# LVDS.net
KiCad netlist of a schematic drawn in Altium Designer
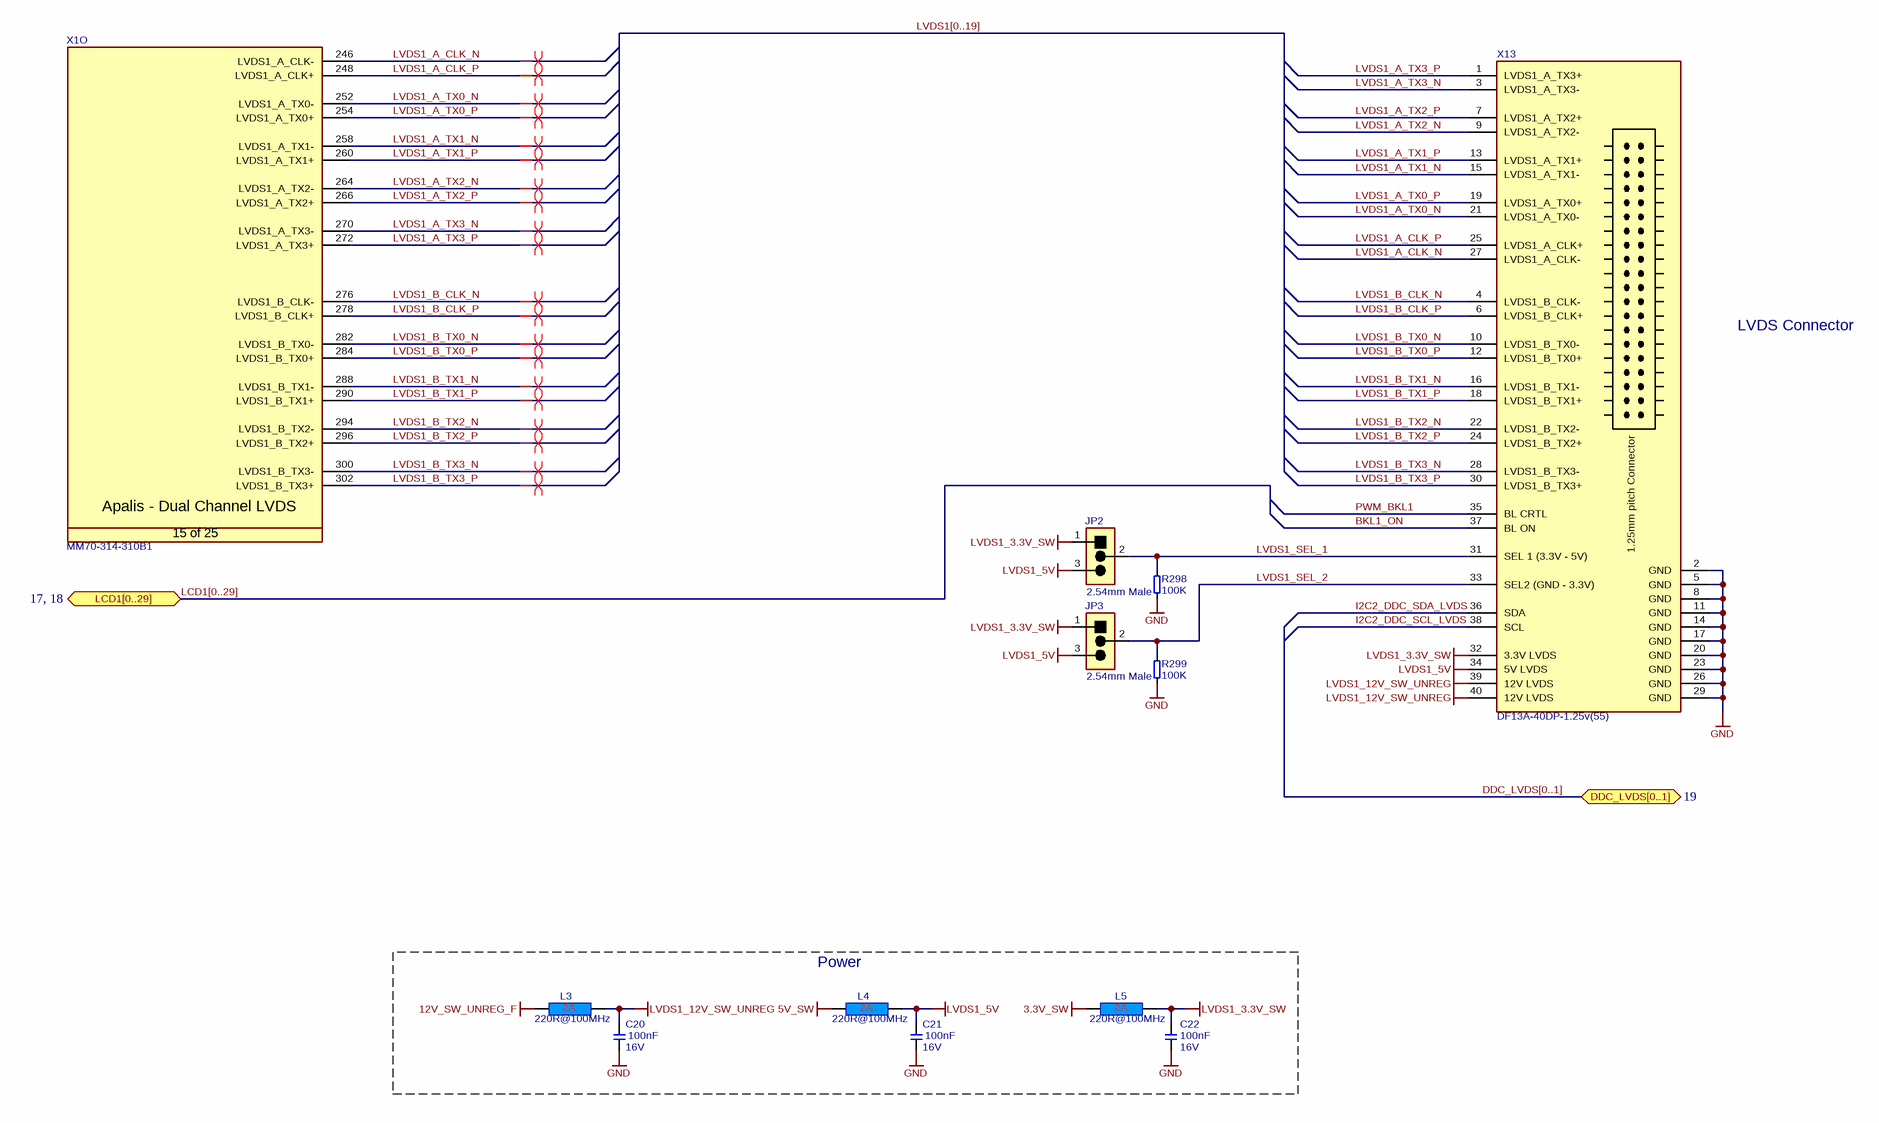
[diagram p0: LVDS.SchDoc]

(export (version "E")
  (design (tool "Eeschema 10.0.6"))
  (components
    (comp (ref "C20")
      (value "100nF")
      (footprint "T_CAPC0603X33N")
      (description "Capacitor Ceramic X7R 100nF 16V 10% 0603")
      (fields (field (name "TOLERANCE") "10%") (field (name "RATING") "16V"))
      (libsource (lib "Apalis Evaluation Board") (part "C-X7R-100nF-16V-10%-0603"))
    )
    (comp (ref "C21")
      (value "100nF")
      (footprint "T_CAPC0603X33N")
      (description "Capacitor Ceramic X7R 100nF 16V 10% 0603")
      (fields (field (name "TOLERANCE") "10%") (field (name "RATING") "16V"))
      (libsource (lib "Apalis Evaluation Board") (part "C-X7R-100nF-16V-10%-0603"))
    )
    (comp (ref "C22")
      (value "100nF")
      (footprint "T_CAPC0603X33N")
      (description "Capacitor Ceramic X7R 100nF 16V 10% 0603")
      (fields (field (name "TOLERANCE") "10%") (field (name "RATING") "16V"))
      (libsource (lib "Apalis Evaluation Board") (part "C-X7R-100nF-16V-10%-0603"))
    )
    (comp (ref "JP2")
      (value "826936-3")
      (footprint "T_TYCO_826936-3")
      (description "Jumper, 3-Pin")
      (libsource (lib "Apalis Evaluation Board") (part "CON-Tyco-826936-3-1X3-2.54mm-JP"))
    )
    (comp (ref "JP3")
      (value "826936-3")
      (footprint "T_TYCO_826936-3")
      (description "Jumper, 3-Pin")
      (libsource (lib "Apalis Evaluation Board") (part "CON-Tyco-826936-3-1X3-2.54mm-JP"))
    )
    (comp (ref "L3")
      (value "220R@100MHz")
      (footprint "INDC1608X95N")
      (description "220R@100MHz 2A EMI FILTER")
      (fields (field (name "TOLERANCE") "25%"))
      (libsource (lib "Apalis Evaluation Board") (part "L-220R@100MHz-2A-25%-0603"))
    )
    (comp (ref "L4")
      (value "220R@100MHz")
      (footprint "INDC1608X95N")
      (description "220R@100MHz 2A EMI FILTER")
      (fields (field (name "TOLERANCE") "25%"))
      (libsource (lib "Apalis Evaluation Board") (part "L-220R@100MHz-2A-25%-0603"))
    )
    (comp (ref "L5")
      (value "220R@100MHz")
      (footprint "INDC1608X95N")
      (description "220R@100MHz 2A EMI FILTER")
      (fields (field (name "TOLERANCE") "25%"))
      (libsource (lib "Apalis Evaluation Board") (part "L-220R@100MHz-2A-25%-0603"))
    )
    (comp (ref "R298")
      (value "100K")
      (footprint "T_RESC0603X30N")
      (description "Resistor 100 Kohm 63mW 5% 0603")
      (fields (field (name "TOLERANCE") "5%"))
      (libsource (lib "Apalis Evaluation Board") (part "R-100KR-63mW-5%-0603"))
    )
    (comp (ref "R299")
      (value "100K")
      (footprint "T_RESC0603X30N")
      (description "Resistor 100 Kohm 63mW 5% 0603")
      (fields (field (name "TOLERANCE") "5%"))
      (libsource (lib "Apalis Evaluation Board") (part "R-100KR-63mW-5%-0603"))
    )
    (comp (ref "X1")
      (value "CON-JAE-MM70-314-310B1-314-0.5mm")
      (footprint "T_JAE_MM70-314-310B1")
      (description "MXM3 Connector")
      (fields (field (name "MANUFACTURER PART NO.") "MM70-314-310B1"))
      (libsource (lib "Apalis Evaluation Board") (part "CON-JAE-MM70-314-310B1-314-0.5mm"))
    )
    (comp (ref "X13")
      (value "CON-Hirose-DF13A-40DP-1.25v(55)-2x10-1mm")
      (footprint "T_HIROSE_DF13A-40DP-1.25V(55)")
      (description "LVDS Connector")
      (fields (field (name "MANUFACTURER PART NO.") "DF13A-40DP-1.25v(55)"))
      (libsource (lib "Apalis Evaluation Board") (part "CON-Hirose-DF13A-40DP-1.25v(55)-2x20-1.25mm"))
    )
  )
  (nets
    (net (code "53") (name "/BKL1_ON") (class "Default")
      (node (ref "X13") (pin "37") (pinfunction "BL_ON_37") (pintype "passive"))
    )
    (net (code "55") (name "/I2C2_DDC_SCL_LVDS") (class "Default")
      (node (ref "X13") (pin "38") (pinfunction "SCL_38") (pintype "passive"))
    )
    (net (code "56") (name "/I2C2_DDC_SDA_LVDS") (class "Default")
      (node (ref "X13") (pin "36") (pinfunction "SDA_36") (pintype "passive"))
    )
    (net (code "59") (name "/LVDS1_A_CLK_N") (class "Default")
      (node (ref "X1") (pin "246") (pinfunction "LVDS1_A_CLK-_246") (pintype "passive"))
      (node (ref "X13") (pin "27") (pinfunction "LVDS1_A_CLK-_27") (pintype "passive"))
    )
    (net (code "60") (name "/LVDS1_A_CLK_P") (class "Default")
      (node (ref "X1") (pin "248") (pinfunction "LVDS1_A_CLK+_248") (pintype "passive"))
      (node (ref "X13") (pin "25") (pinfunction "LVDS1_A_CLK+_25") (pintype "passive"))
    )
    (net (code "61") (name "/LVDS1_A_TX0_N") (class "Default")
      (node (ref "X1") (pin "252") (pinfunction "LVDS1_A_TX0-_252") (pintype "passive"))
      (node (ref "X13") (pin "21") (pinfunction "LVDS1_A_TX0-_21") (pintype "passive"))
    )
    (net (code "62") (name "/LVDS1_A_TX0_P") (class "Default")
      (node (ref "X1") (pin "254") (pinfunction "LVDS1_A_TX0+_254") (pintype "passive"))
      (node (ref "X13") (pin "19") (pinfunction "LVDS1_A_TX0+_19") (pintype "passive"))
    )
    (net (code "63") (name "/LVDS1_A_TX1_N") (class "Default")
      (node (ref "X1") (pin "258") (pinfunction "LVDS1_A_TX1-_258") (pintype "passive"))
      (node (ref "X13") (pin "15") (pinfunction "LVDS1_A_TX1-_15") (pintype "passive"))
    )
    (net (code "64") (name "/LVDS1_A_TX1_P") (class "Default")
      (node (ref "X1") (pin "260") (pinfunction "LVDS1_A_TX1+_260") (pintype "passive"))
      (node (ref "X13") (pin "13") (pinfunction "LVDS1_A_TX1+_13") (pintype "passive"))
    )
    (net (code "65") (name "/LVDS1_A_TX2_N") (class "Default")
      (node (ref "X1") (pin "264") (pinfunction "LVDS1_A_TX2-_264") (pintype "passive"))
      (node (ref "X13") (pin "9") (pinfunction "LVDS1_A_TX2-_9") (pintype "passive"))
    )
    (net (code "66") (name "/LVDS1_A_TX2_P") (class "Default")
      (node (ref "X1") (pin "266") (pinfunction "LVDS1_A_TX2+_266") (pintype "passive"))
      (node (ref "X13") (pin "7") (pinfunction "LVDS1_A_TX2+_7") (pintype "passive"))
    )
    (net (code "67") (name "/LVDS1_A_TX3_N") (class "Default")
      (node (ref "X1") (pin "270") (pinfunction "LVDS1_A_TX3-_270") (pintype "passive"))
      (node (ref "X13") (pin "3") (pinfunction "LVDS1_A_TX3-_3") (pintype "passive"))
    )
    (net (code "68") (name "/LVDS1_A_TX3_P") (class "Default")
      (node (ref "X1") (pin "272") (pinfunction "LVDS1_A_TX3+_272") (pintype "passive"))
      (node (ref "X13") (pin "1") (pinfunction "LVDS1_A_TX3+_1") (pintype "passive"))
    )
    (net (code "69") (name "/LVDS1_B_CLK_N") (class "Default")
      (node (ref "X1") (pin "276") (pinfunction "LVDS1_B_CLK-_276") (pintype "passive"))
      (node (ref "X13") (pin "4") (pinfunction "LVDS1_B_CLK-_4") (pintype "passive"))
    )
    (net (code "70") (name "/LVDS1_B_CLK_P") (class "Default")
      (node (ref "X1") (pin "278") (pinfunction "LVDS1_B_CLK+_278") (pintype "passive"))
      (node (ref "X13") (pin "6") (pinfunction "LVDS1_B_CLK+_6") (pintype "passive"))
    )
    (net (code "71") (name "/LVDS1_B_TX0_N") (class "Default")
      (node (ref "X1") (pin "282") (pinfunction "LVDS1_B_TX0-_282") (pintype "passive"))
      (node (ref "X13") (pin "10") (pinfunction "LVDS1_B_TX0-_10") (pintype "passive"))
    )
    (net (code "72") (name "/LVDS1_B_TX0_P") (class "Default")
      (node (ref "X1") (pin "284") (pinfunction "LVDS1_B_TX0+_284") (pintype "passive"))
      (node (ref "X13") (pin "12") (pinfunction "LVDS1_B_TX0+_12") (pintype "passive"))
    )
    (net (code "73") (name "/LVDS1_B_TX1_N") (class "Default")
      (node (ref "X1") (pin "288") (pinfunction "LVDS1_B_TX1-_288") (pintype "passive"))
      (node (ref "X13") (pin "16") (pinfunction "LVDS1_B_TX1-_16") (pintype "passive"))
    )
    (net (code "74") (name "/LVDS1_B_TX1_P") (class "Default")
      (node (ref "X1") (pin "290") (pinfunction "LVDS1_B_TX1+_290") (pintype "passive"))
      (node (ref "X13") (pin "18") (pinfunction "LVDS1_B_TX1+_18") (pintype "passive"))
    )
    (net (code "75") (name "/LVDS1_B_TX2_N") (class "Default")
      (node (ref "X1") (pin "294") (pinfunction "LVDS1_B_TX2-_294") (pintype "passive"))
      (node (ref "X13") (pin "22") (pinfunction "LVDS1_B_TX2-_22") (pintype "passive"))
    )
    (net (code "76") (name "/LVDS1_B_TX2_P") (class "Default")
      (node (ref "X1") (pin "296") (pinfunction "LVDS1_B_TX2+_296") (pintype "passive"))
      (node (ref "X13") (pin "24") (pinfunction "LVDS1_B_TX2+_24") (pintype "passive"))
    )
    (net (code "77") (name "/LVDS1_B_TX3_N") (class "Default")
      (node (ref "X1") (pin "300") (pinfunction "LVDS1_B_TX3-_300") (pintype "passive"))
      (node (ref "X13") (pin "28") (pinfunction "LVDS1_B_TX3-_28") (pintype "passive"))
    )
    (net (code "78") (name "/LVDS1_B_TX3_P") (class "Default")
      (node (ref "X1") (pin "302") (pinfunction "LVDS1_B_TX3+_302") (pintype "passive"))
      (node (ref "X13") (pin "30") (pinfunction "LVDS1_B_TX3+_30") (pintype "passive"))
    )
    (net (code "79") (name "/LVDS1_SEL_1") (class "Default")
      (node (ref "JP2") (pin "2") (pinfunction "2_2") (pintype "passive"))
      (node (ref "R298") (pin "2") (pinfunction "2_2") (pintype "passive"))
      (node (ref "X13") (pin "31") (pinfunction "SEL_1_(3.3V_-_5V)_31") (pintype "passive"))
    )
    (net (code "80") (name "/LVDS1_SEL_2") (class "Default")
      (node (ref "JP3") (pin "2") (pinfunction "2_2") (pintype "passive"))
      (node (ref "R299") (pin "2") (pinfunction "2_2") (pintype "passive"))
      (node (ref "X13") (pin "33") (pinfunction "SEL2_(GND_-_3.3V)_33") (pintype "passive"))
    )
    (net (code "81") (name "/PWM_BKL1") (class "Default")
      (node (ref "X13") (pin "35") (pinfunction "BL_CRTL_35") (pintype "passive"))
    )
    (net (code "82") (name "3.3V_SW") (class "Default")
      (node (ref "L5") (pin "1") (pinfunction "1_1") (pintype "passive"))
    )
    (net (code "83") (name "5V_SW") (class "Default")
      (node (ref "L4") (pin "1") (pinfunction "1_1") (pintype "passive"))
    )
    (net (code "84") (name "12V_SW_UNREG_F") (class "Default")
      (node (ref "L3") (pin "1") (pinfunction "1_1") (pintype "passive"))
    )
    (net (code "85") (name "GND") (class "Default")
      (node (ref "C20") (pin "1") (pinfunction "1_1") (pintype "passive"))
      (node (ref "C21") (pin "1") (pinfunction "1_1") (pintype "passive"))
      (node (ref "C22") (pin "1") (pinfunction "1_1") (pintype "passive"))
      (node (ref "R298") (pin "1") (pinfunction "1_1") (pintype "passive"))
      (node (ref "R299") (pin "1") (pinfunction "1_1") (pintype "passive"))
      (node (ref "X13") (pin "11") (pinfunction "GND_11") (pintype "passive"))
      (node (ref "X13") (pin "14") (pinfunction "GND_14") (pintype "passive"))
      (node (ref "X13") (pin "17") (pinfunction "GND_17") (pintype "passive"))
      (node (ref "X13") (pin "2") (pinfunction "GND_2") (pintype "passive"))
      (node (ref "X13") (pin "20") (pinfunction "GND_20") (pintype "passive"))
      (node (ref "X13") (pin "23") (pinfunction "GND_23") (pintype "passive"))
      (node (ref "X13") (pin "26") (pinfunction "GND_26") (pintype "passive"))
      (node (ref "X13") (pin "29") (pinfunction "GND_29") (pintype "passive"))
      (node (ref "X13") (pin "5") (pinfunction "GND_5") (pintype "passive"))
      (node (ref "X13") (pin "8") (pinfunction "GND_8") (pintype "passive"))
    )
    (net (code "86") (name "LVDS1_3.3V_SW") (class "Default")
      (node (ref "C22") (pin "2") (pinfunction "2_2") (pintype "passive"))
      (node (ref "JP2") (pin "1") (pinfunction "1_1") (pintype "passive"))
      (node (ref "JP3") (pin "1") (pinfunction "1_1") (pintype "passive"))
      (node (ref "L5") (pin "2") (pinfunction "2_2") (pintype "passive"))
      (node (ref "X13") (pin "32") (pinfunction "3.3V_LVDS_32") (pintype "passive"))
    )
    (net (code "87") (name "LVDS1_5V") (class "Default")
      (node (ref "C21") (pin "2") (pinfunction "2_2") (pintype "passive"))
      (node (ref "JP2") (pin "3") (pinfunction "3_3") (pintype "passive"))
      (node (ref "JP3") (pin "3") (pinfunction "3_3") (pintype "passive"))
      (node (ref "L4") (pin "2") (pinfunction "2_2") (pintype "passive"))
      (node (ref "X13") (pin "34") (pinfunction "5V_LVDS_34") (pintype "passive"))
    )
    (net (code "88") (name "LVDS1_12V_SW_UNREG") (class "Default")
      (node (ref "C20") (pin "2") (pinfunction "2_2") (pintype "passive"))
      (node (ref "L3") (pin "2") (pinfunction "2_2") (pintype "passive"))
      (node (ref "X13") (pin "39") (pinfunction "12V_LVDS_39") (pintype "passive"))
      (node (ref "X13") (pin "40") (pinfunction "12V_LVDS_40") (pintype "passive"))
    )
  )
)
